# schaltplan_v2.net
KiCad netlist of a schematic drawn in EAGLE
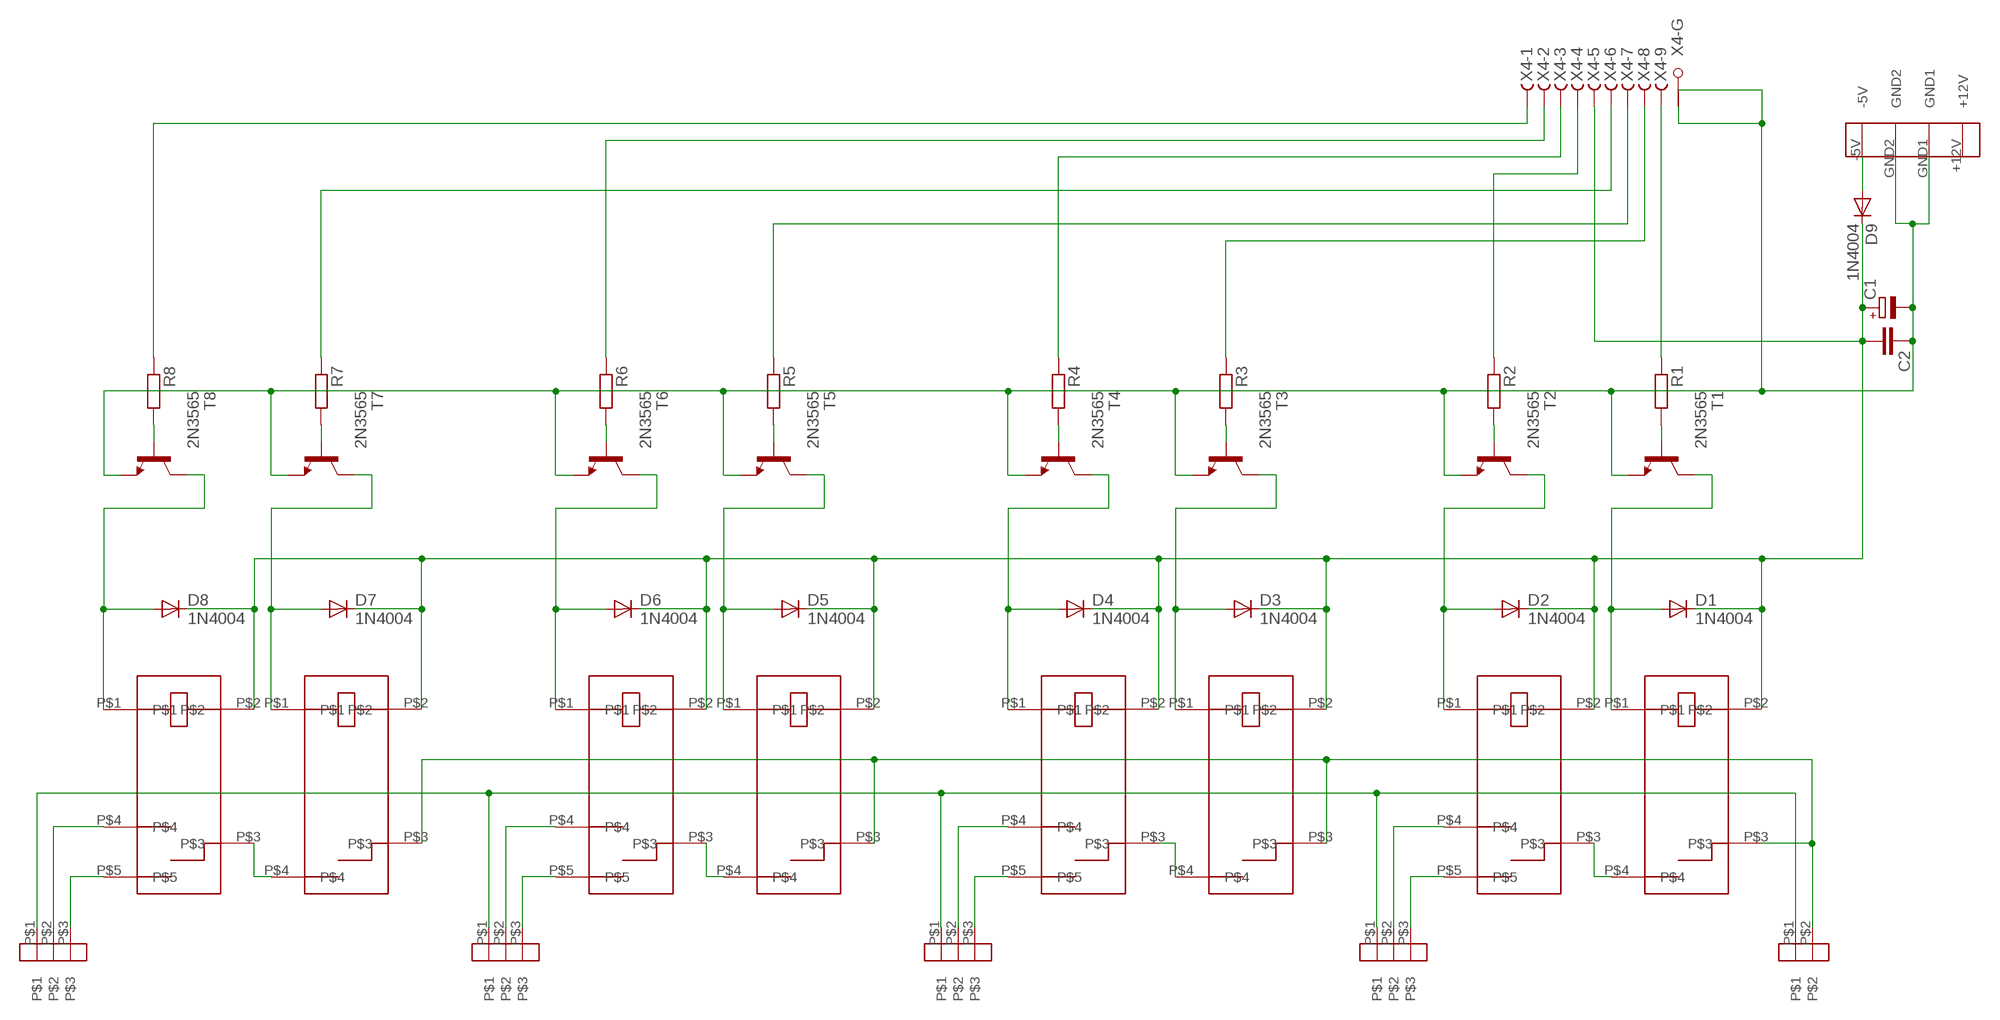
[diagram p0: schematic, sheet 1]

(export (version "E")
  (design (tool "Eeschema 10.0.6"))
  (components
    (comp (ref "C1")
      (value "CPOL-EUE3.5-8")
      (footprint "eagle-import:E3,5-8")
      (libsource (lib "eagle-import") (part "CPOL-EUE3.5-8"))
    )
    (comp (ref "C2")
      (value "C-EU025-030X050")
      (footprint "eagle-import:C025-030X050")
      (libsource (lib "eagle-import") (part "C-EU025-030X050"))
    )
    (comp (ref "D1")
      (value "1N4004")
      (footprint "eagle-import:DO41-10")
      (libsource (lib "eagle-import") (part "1N4004"))
    )
    (comp (ref "D2")
      (value "1N4004")
      (footprint "eagle-import:DO41-10")
      (libsource (lib "eagle-import") (part "1N4004"))
    )
    (comp (ref "D3")
      (value "1N4004")
      (footprint "eagle-import:DO41-10")
      (libsource (lib "eagle-import") (part "1N4004"))
    )
    (comp (ref "D4")
      (value "1N4004")
      (footprint "eagle-import:DO41-10")
      (libsource (lib "eagle-import") (part "1N4004"))
    )
    (comp (ref "D5")
      (value "1N4004")
      (footprint "eagle-import:DO41-10")
      (libsource (lib "eagle-import") (part "1N4004"))
    )
    (comp (ref "D6")
      (value "1N4004")
      (footprint "eagle-import:DO41-10")
      (libsource (lib "eagle-import") (part "1N4004"))
    )
    (comp (ref "D7")
      (value "1N4004")
      (footprint "eagle-import:DO41-10")
      (libsource (lib "eagle-import") (part "1N4004"))
    )
    (comp (ref "D8")
      (value "1N4004")
      (footprint "eagle-import:DO41-10")
      (libsource (lib "eagle-import") (part "1N4004"))
    )
    (comp (ref "D9")
      (value "1N4004")
      (footprint "eagle-import:DO41-10")
      (libsource (lib "eagle-import") (part "1N4004"))
    )
    (comp (ref "R1")
      (value "R-EU_0207/7")
      (footprint "eagle-import:0207_7")
      (libsource (lib "eagle-import") (part "R-EU_0207/7"))
    )
    (comp (ref "R2")
      (value "R-EU_0207/7")
      (footprint "eagle-import:0207_7")
      (libsource (lib "eagle-import") (part "R-EU_0207/7"))
    )
    (comp (ref "R3")
      (value "R-EU_0207/7")
      (footprint "eagle-import:0207_7")
      (libsource (lib "eagle-import") (part "R-EU_0207/7"))
    )
    (comp (ref "R4")
      (value "R-EU_0207/7")
      (footprint "eagle-import:0207_7")
      (libsource (lib "eagle-import") (part "R-EU_0207/7"))
    )
    (comp (ref "R5")
      (value "R-EU_0207/7")
      (footprint "eagle-import:0207_7")
      (libsource (lib "eagle-import") (part "R-EU_0207/7"))
    )
    (comp (ref "R6")
      (value "R-EU_0207/7")
      (footprint "eagle-import:0207_7")
      (libsource (lib "eagle-import") (part "R-EU_0207/7"))
    )
    (comp (ref "R7")
      (value "R-EU_0207/7")
      (footprint "eagle-import:0207_7")
      (libsource (lib "eagle-import") (part "R-EU_0207/7"))
    )
    (comp (ref "R8")
      (value "R-EU_0207/7")
      (footprint "eagle-import:0207_7")
      (libsource (lib "eagle-import") (part "R-EU_0207/7"))
    )
    (comp (ref "T1")
      (value "2N3565")
      (footprint "eagle-import:TO92")
      (libsource (lib "eagle-import") (part "2N3565"))
    )
    (comp (ref "T2")
      (value "2N3565")
      (footprint "eagle-import:TO92")
      (libsource (lib "eagle-import") (part "2N3565"))
    )
    (comp (ref "T3")
      (value "2N3565")
      (footprint "eagle-import:TO92")
      (libsource (lib "eagle-import") (part "2N3565"))
    )
    (comp (ref "T4")
      (value "2N3565")
      (footprint "eagle-import:TO92")
      (libsource (lib "eagle-import") (part "2N3565"))
    )
    (comp (ref "T5")
      (value "2N3565")
      (footprint "eagle-import:TO92")
      (libsource (lib "eagle-import") (part "2N3565"))
    )
    (comp (ref "T6")
      (value "2N3565")
      (footprint "eagle-import:TO92")
      (libsource (lib "eagle-import") (part "2N3565"))
    )
    (comp (ref "T7")
      (value "2N3565")
      (footprint "eagle-import:TO92")
      (libsource (lib "eagle-import") (part "2N3565"))
    )
    (comp (ref "T8")
      (value "2N3565")
      (footprint "eagle-import:TO92")
      (libsource (lib "eagle-import") (part "2N3565"))
    )
    (comp (ref "U$1")
      (value "JS_05_MN_KT")
      (footprint "eagle-import:JS_05_MN_KT")
      (libsource (lib "eagle-import") (part "JS_05_MN_KT"))
    )
    (comp (ref "U$2")
      (value "JS_05_N_K")
      (footprint "eagle-import:JS_05_N_K")
      (libsource (lib "eagle-import") (part "JS_05_N_K"))
    )
    (comp (ref "U$3")
      (value "JS_05_MN_KT")
      (footprint "eagle-import:JS_05_MN_KT")
      (libsource (lib "eagle-import") (part "JS_05_MN_KT"))
    )
    (comp (ref "U$4")
      (value "JS_05_N_K")
      (footprint "eagle-import:JS_05_N_K")
      (libsource (lib "eagle-import") (part "JS_05_N_K"))
    )
    (comp (ref "U$5")
      (value "JS_05_MN_KT")
      (footprint "eagle-import:JS_05_MN_KT")
      (libsource (lib "eagle-import") (part "JS_05_MN_KT"))
    )
    (comp (ref "U$6")
      (value "JS_05_N_K")
      (footprint "eagle-import:JS_05_N_K")
      (libsource (lib "eagle-import") (part "JS_05_N_K"))
    )
    (comp (ref "U$7")
      (value "JS_05_MN_KT")
      (footprint "eagle-import:JS_05_MN_KT")
      (libsource (lib "eagle-import") (part "JS_05_MN_KT"))
    )
    (comp (ref "U$8")
      (value "JS_05_N_K")
      (footprint "eagle-import:JS_05_N_K")
      (libsource (lib "eagle-import") (part "JS_05_N_K"))
    )
    (comp (ref "U$9")
      (value "WAGO_734_262")
      (footprint "eagle-import:WAGO_734_262")
      (libsource (lib "eagle-import") (part "WAGO_734_262"))
    )
    (comp (ref "U$10")
      (value "WAGO_734_263")
      (footprint "eagle-import:WAGO_734_263")
      (libsource (lib "eagle-import") (part "WAGO_734_263"))
    )
    (comp (ref "U$11")
      (value "WAGO_734_263")
      (footprint "eagle-import:WAGO_734_263")
      (libsource (lib "eagle-import") (part "WAGO_734_263"))
    )
    (comp (ref "U$12")
      (value "WAGO_734_263")
      (footprint "eagle-import:WAGO_734_263")
      (libsource (lib "eagle-import") (part "WAGO_734_263"))
    )
    (comp (ref "U$13")
      (value "WAGO_734_263")
      (footprint "eagle-import:WAGO_734_263")
      (libsource (lib "eagle-import") (part "WAGO_734_263"))
    )
    (comp (ref "U$14")
      (value "PSW_5")
      (footprint "eagle-import:PSW_5")
      (libsource (lib "eagle-import") (part "PSW_5"))
    )
    (comp (ref "X4")
      (value "F09HPS")
      (footprint "eagle-import:F09HP")
      (libsource (lib "eagle-import") (part "F09HPS"))
    )
  )
  (nets
    (net (code "1") (name "Net-(D9-PadA)") (class "Default")
      (node (ref "D9") (pin "A") (pinfunction "A_A") (pintype "passive"))
      (node (ref "U$14") (pin "-5V") (pinfunction "-5V_-5V") (pintype "bidirectional"))
    )
    (net (code "2") (name "Net-(T1-B)") (class "Default")
      (node (ref "R1") (pin "2") (pinfunction "2_2") (pintype "passive"))
      (node (ref "T1") (pin "2") (pinfunction "B_2") (pintype "passive"))
    )
    (net (code "3") (name "Net-(T1-C)") (class "Default")
      (node (ref "D1") (pin "A") (pinfunction "A_A") (pintype "passive"))
      (node (ref "T1") (pin "1") (pinfunction "C_1") (pintype "passive"))
      (node (ref "U$1") (pin "P$1") (pinfunction "P$1_P$1") (pintype "bidirectional"))
    )
    (net (code "4") (name "Net-(T1-E)") (class "Default")
      (node (ref "C1") (pin "-") (pinfunction "-_-") (pintype "passive"))
      (node (ref "C2") (pin "1") (pinfunction "1_1") (pintype "passive"))
      (node (ref "T1") (pin "3") (pinfunction "E_3") (pintype "passive"))
      (node (ref "T2") (pin "3") (pinfunction "E_3") (pintype "passive"))
      (node (ref "T3") (pin "3") (pinfunction "E_3") (pintype "passive"))
      (node (ref "T4") (pin "3") (pinfunction "E_3") (pintype "passive"))
      (node (ref "T5") (pin "3") (pinfunction "E_3") (pintype "passive"))
      (node (ref "T6") (pin "3") (pinfunction "E_3") (pintype "passive"))
      (node (ref "T7") (pin "3") (pinfunction "E_3") (pintype "passive"))
      (node (ref "T8") (pin "3") (pinfunction "E_3") (pintype "passive"))
      (node (ref "U$14") (pin "GND1") (pinfunction "GND1_GND1") (pintype "bidirectional"))
      (node (ref "U$14") (pin "GND2") (pinfunction "GND2_GND2") (pintype "bidirectional"))
      (node (ref "X4") (pin "G1") (pinfunction "G1_G1") (pintype "passive"))
      (node (ref "X4") (pin "G2") (pinfunction "G2_G2") (pintype "passive"))
    )
    (net (code "5") (name "Net-(T2-B)") (class "Default")
      (node (ref "R2") (pin "2") (pinfunction "2_2") (pintype "passive"))
      (node (ref "T2") (pin "2") (pinfunction "B_2") (pintype "passive"))
    )
    (net (code "6") (name "Net-(T2-C)") (class "Default")
      (node (ref "D2") (pin "A") (pinfunction "A_A") (pintype "passive"))
      (node (ref "T2") (pin "1") (pinfunction "C_1") (pintype "passive"))
      (node (ref "U$2") (pin "P$1") (pinfunction "P$1_P$1") (pintype "bidirectional"))
    )
    (net (code "7") (name "Net-(T3-B)") (class "Default")
      (node (ref "R3") (pin "2") (pinfunction "2_2") (pintype "passive"))
      (node (ref "T3") (pin "2") (pinfunction "B_2") (pintype "passive"))
    )
    (net (code "8") (name "Net-(T3-C)") (class "Default")
      (node (ref "D3") (pin "A") (pinfunction "A_A") (pintype "passive"))
      (node (ref "T3") (pin "1") (pinfunction "C_1") (pintype "passive"))
      (node (ref "U$3") (pin "P$1") (pinfunction "P$1_P$1") (pintype "bidirectional"))
    )
    (net (code "9") (name "Net-(T4-B)") (class "Default")
      (node (ref "R4") (pin "2") (pinfunction "2_2") (pintype "passive"))
      (node (ref "T4") (pin "2") (pinfunction "B_2") (pintype "passive"))
    )
    (net (code "10") (name "Net-(T4-C)") (class "Default")
      (node (ref "D4") (pin "A") (pinfunction "A_A") (pintype "passive"))
      (node (ref "T4") (pin "1") (pinfunction "C_1") (pintype "passive"))
      (node (ref "U$4") (pin "P$1") (pinfunction "P$1_P$1") (pintype "bidirectional"))
    )
    (net (code "11") (name "Net-(T5-B)") (class "Default")
      (node (ref "R5") (pin "2") (pinfunction "2_2") (pintype "passive"))
      (node (ref "T5") (pin "2") (pinfunction "B_2") (pintype "passive"))
    )
    (net (code "12") (name "Net-(T5-C)") (class "Default")
      (node (ref "D5") (pin "A") (pinfunction "A_A") (pintype "passive"))
      (node (ref "T5") (pin "1") (pinfunction "C_1") (pintype "passive"))
      (node (ref "U$5") (pin "P$1") (pinfunction "P$1_P$1") (pintype "bidirectional"))
    )
    (net (code "13") (name "Net-(T6-B)") (class "Default")
      (node (ref "R6") (pin "2") (pinfunction "2_2") (pintype "passive"))
      (node (ref "T6") (pin "2") (pinfunction "B_2") (pintype "passive"))
    )
    (net (code "14") (name "Net-(T6-C)") (class "Default")
      (node (ref "D6") (pin "A") (pinfunction "A_A") (pintype "passive"))
      (node (ref "T6") (pin "1") (pinfunction "C_1") (pintype "passive"))
      (node (ref "U$6") (pin "P$1") (pinfunction "P$1_P$1") (pintype "bidirectional"))
    )
    (net (code "15") (name "Net-(T7-B)") (class "Default")
      (node (ref "R7") (pin "2") (pinfunction "2_2") (pintype "passive"))
      (node (ref "T7") (pin "2") (pinfunction "B_2") (pintype "passive"))
    )
    (net (code "16") (name "Net-(T7-C)") (class "Default")
      (node (ref "D7") (pin "A") (pinfunction "A_A") (pintype "passive"))
      (node (ref "T7") (pin "1") (pinfunction "C_1") (pintype "passive"))
      (node (ref "U$7") (pin "P$1") (pinfunction "P$1_P$1") (pintype "bidirectional"))
    )
    (net (code "17") (name "Net-(T8-B)") (class "Default")
      (node (ref "R8") (pin "2") (pinfunction "2_2") (pintype "passive"))
      (node (ref "T8") (pin "2") (pinfunction "B_2") (pintype "passive"))
    )
    (net (code "18") (name "Net-(T8-C)") (class "Default")
      (node (ref "D8") (pin "A") (pinfunction "A_A") (pintype "passive"))
      (node (ref "T8") (pin "1") (pinfunction "C_1") (pintype "passive"))
      (node (ref "U$8") (pin "P$1") (pinfunction "P$1_P$1") (pintype "bidirectional"))
    )
    (net (code "19") (name "Net-(U$1-PadP$3)") (class "Default")
      (node (ref "U$1") (pin "P$3") (pinfunction "P$3_P$3") (pintype "bidirectional"))
      (node (ref "U$3") (pin "P$3") (pinfunction "P$3_P$3") (pintype "bidirectional"))
      (node (ref "U$5") (pin "P$3") (pinfunction "P$3_P$3") (pintype "bidirectional"))
      (node (ref "U$7") (pin "P$3") (pinfunction "P$3_P$3") (pintype "bidirectional"))
      (node (ref "U$9") (pin "P$2") (pinfunction "P$2_P$2") (pintype "bidirectional"))
    )
    (net (code "20") (name "Net-(U$1-PadP$4)") (class "Default")
      (node (ref "U$1") (pin "P$4") (pinfunction "P$4_P$4") (pintype "bidirectional"))
      (node (ref "U$2") (pin "P$3") (pinfunction "P$3_P$3") (pintype "bidirectional"))
    )
    (net (code "21") (name "Net-(U$3-PadP$4)") (class "Default")
      (node (ref "U$3") (pin "P$4") (pinfunction "P$4_P$4") (pintype "bidirectional"))
      (node (ref "U$4") (pin "P$3") (pinfunction "P$3_P$3") (pintype "bidirectional"))
    )
    (net (code "22") (name "Net-(U$5-PadP$4)") (class "Default")
      (node (ref "U$5") (pin "P$4") (pinfunction "P$4_P$4") (pintype "bidirectional"))
      (node (ref "U$6") (pin "P$3") (pinfunction "P$3_P$3") (pintype "bidirectional"))
    )
    (net (code "23") (name "Net-(U$7-PadP$4)") (class "Default")
      (node (ref "U$7") (pin "P$4") (pinfunction "P$4_P$4") (pintype "bidirectional"))
      (node (ref "U$8") (pin "P$3") (pinfunction "P$3_P$3") (pintype "bidirectional"))
    )
    (net (code "24") (name "Net-(U$10-PadP$1)") (class "Default")
      (node (ref "U$10") (pin "P$1") (pinfunction "P$1_P$1") (pintype "bidirectional"))
      (node (ref "U$11") (pin "P$1") (pinfunction "P$1_P$1") (pintype "bidirectional"))
      (node (ref "U$12") (pin "P$1") (pinfunction "P$1_P$1") (pintype "bidirectional"))
      (node (ref "U$13") (pin "P$1") (pinfunction "P$1_P$1") (pintype "bidirectional"))
      (node (ref "U$9") (pin "P$1") (pinfunction "P$1_P$1") (pintype "bidirectional"))
    )
    (net (code "25") (name "Net-(U$10-PadP$2)") (class "Default")
      (node (ref "U$10") (pin "P$2") (pinfunction "P$2_P$2") (pintype "bidirectional"))
      (node (ref "U$2") (pin "P$4") (pinfunction "P$4_P$4") (pintype "bidirectional"))
    )
    (net (code "26") (name "Net-(U$10-PadP$3)") (class "Default")
      (node (ref "U$10") (pin "P$3") (pinfunction "P$3_P$3") (pintype "bidirectional"))
      (node (ref "U$2") (pin "P$5") (pinfunction "P$5_P$5") (pintype "bidirectional"))
    )
    (net (code "27") (name "Net-(U$11-PadP$2)") (class "Default")
      (node (ref "U$11") (pin "P$2") (pinfunction "P$2_P$2") (pintype "bidirectional"))
      (node (ref "U$4") (pin "P$4") (pinfunction "P$4_P$4") (pintype "bidirectional"))
    )
    (net (code "28") (name "Net-(U$11-PadP$3)") (class "Default")
      (node (ref "U$11") (pin "P$3") (pinfunction "P$3_P$3") (pintype "bidirectional"))
      (node (ref "U$4") (pin "P$5") (pinfunction "P$5_P$5") (pintype "bidirectional"))
    )
    (net (code "29") (name "Net-(U$12-PadP$2)") (class "Default")
      (node (ref "U$12") (pin "P$2") (pinfunction "P$2_P$2") (pintype "bidirectional"))
      (node (ref "U$6") (pin "P$4") (pinfunction "P$4_P$4") (pintype "bidirectional"))
    )
    (net (code "30") (name "Net-(U$12-PadP$3)") (class "Default")
      (node (ref "U$12") (pin "P$3") (pinfunction "P$3_P$3") (pintype "bidirectional"))
      (node (ref "U$6") (pin "P$5") (pinfunction "P$5_P$5") (pintype "bidirectional"))
    )
    (net (code "31") (name "Net-(U$13-PadP$2)") (class "Default")
      (node (ref "U$13") (pin "P$2") (pinfunction "P$2_P$2") (pintype "bidirectional"))
      (node (ref "U$8") (pin "P$4") (pinfunction "P$4_P$4") (pintype "bidirectional"))
    )
    (net (code "32") (name "Net-(U$13-PadP$3)") (class "Default")
      (node (ref "U$13") (pin "P$3") (pinfunction "P$3_P$3") (pintype "bidirectional"))
      (node (ref "U$8") (pin "P$5") (pinfunction "P$5_P$5") (pintype "bidirectional"))
    )
    (net (code "33") (name "Net-(X4A-F)") (class "Default")
      (node (ref "R8") (pin "1") (pinfunction "1_1") (pintype "passive"))
      (node (ref "X4") (pin "1") (pinfunction "F_1") (pintype "passive"))
    )
    (net (code "34") (name "Net-(X4B-F)") (class "Default")
      (node (ref "R6") (pin "1") (pinfunction "1_1") (pintype "passive"))
      (node (ref "X4") (pin "2") (pinfunction "F_2") (pintype "passive"))
    )
    (net (code "35") (name "Net-(X4C-F)") (class "Default")
      (node (ref "R4") (pin "1") (pinfunction "1_1") (pintype "passive"))
      (node (ref "X4") (pin "3") (pinfunction "F_3") (pintype "passive"))
    )
    (net (code "36") (name "Net-(X4D-F)") (class "Default")
      (node (ref "R2") (pin "1") (pinfunction "1_1") (pintype "passive"))
      (node (ref "X4") (pin "4") (pinfunction "F_4") (pintype "passive"))
    )
    (net (code "37") (name "Net-(X4E-F)") (class "Default")
      (node (ref "C1") (pin "+") (pinfunction "+_+") (pintype "passive"))
      (node (ref "C2") (pin "2") (pinfunction "2_2") (pintype "passive"))
      (node (ref "D1") (pin "C") (pinfunction "C_C") (pintype "passive"))
      (node (ref "D2") (pin "C") (pinfunction "C_C") (pintype "passive"))
      (node (ref "D3") (pin "C") (pinfunction "C_C") (pintype "passive"))
      (node (ref "D4") (pin "C") (pinfunction "C_C") (pintype "passive"))
      (node (ref "D5") (pin "C") (pinfunction "C_C") (pintype "passive"))
      (node (ref "D6") (pin "C") (pinfunction "C_C") (pintype "passive"))
      (node (ref "D7") (pin "C") (pinfunction "C_C") (pintype "passive"))
      (node (ref "D8") (pin "C") (pinfunction "C_C") (pintype "passive"))
      (node (ref "D9") (pin "C") (pinfunction "C_C") (pintype "passive"))
      (node (ref "U$1") (pin "P$2") (pinfunction "P$2_P$2") (pintype "bidirectional"))
      (node (ref "U$2") (pin "P$2") (pinfunction "P$2_P$2") (pintype "bidirectional"))
      (node (ref "U$3") (pin "P$2") (pinfunction "P$2_P$2") (pintype "bidirectional"))
      (node (ref "U$4") (pin "P$2") (pinfunction "P$2_P$2") (pintype "bidirectional"))
      (node (ref "U$5") (pin "P$2") (pinfunction "P$2_P$2") (pintype "bidirectional"))
      (node (ref "U$6") (pin "P$2") (pinfunction "P$2_P$2") (pintype "bidirectional"))
      (node (ref "U$7") (pin "P$2") (pinfunction "P$2_P$2") (pintype "bidirectional"))
      (node (ref "U$8") (pin "P$2") (pinfunction "P$2_P$2") (pintype "bidirectional"))
      (node (ref "X4") (pin "5") (pinfunction "F_5") (pintype "passive"))
    )
    (net (code "38") (name "Net-(X4F-F)") (class "Default")
      (node (ref "R7") (pin "1") (pinfunction "1_1") (pintype "passive"))
      (node (ref "X4") (pin "6") (pinfunction "F_6") (pintype "passive"))
    )
    (net (code "39") (name "Net-(X4G-F)") (class "Default")
      (node (ref "R5") (pin "1") (pinfunction "1_1") (pintype "passive"))
      (node (ref "X4") (pin "7") (pinfunction "F_7") (pintype "passive"))
    )
    (net (code "40") (name "Net-(X4H-F)") (class "Default")
      (node (ref "R3") (pin "1") (pinfunction "1_1") (pintype "passive"))
      (node (ref "X4") (pin "8") (pinfunction "F_8") (pintype "passive"))
    )
    (net (code "41") (name "Net-(X4I-F)") (class "Default")
      (node (ref "R1") (pin "1") (pinfunction "1_1") (pintype "passive"))
      (node (ref "X4") (pin "9") (pinfunction "F_9") (pintype "passive"))
    )
    (net (code "42") (name "unconnected-(U$14-Pad+12V)") (class "Default")
      (node (ref "U$14") (pin "+12V") (pinfunction "+12V_+12V") (pintype "bidirectional"))
    )
  )
)
